# Power_and_system_Page_7.net
KiCad netlist of a schematic drawn in Altium Designer
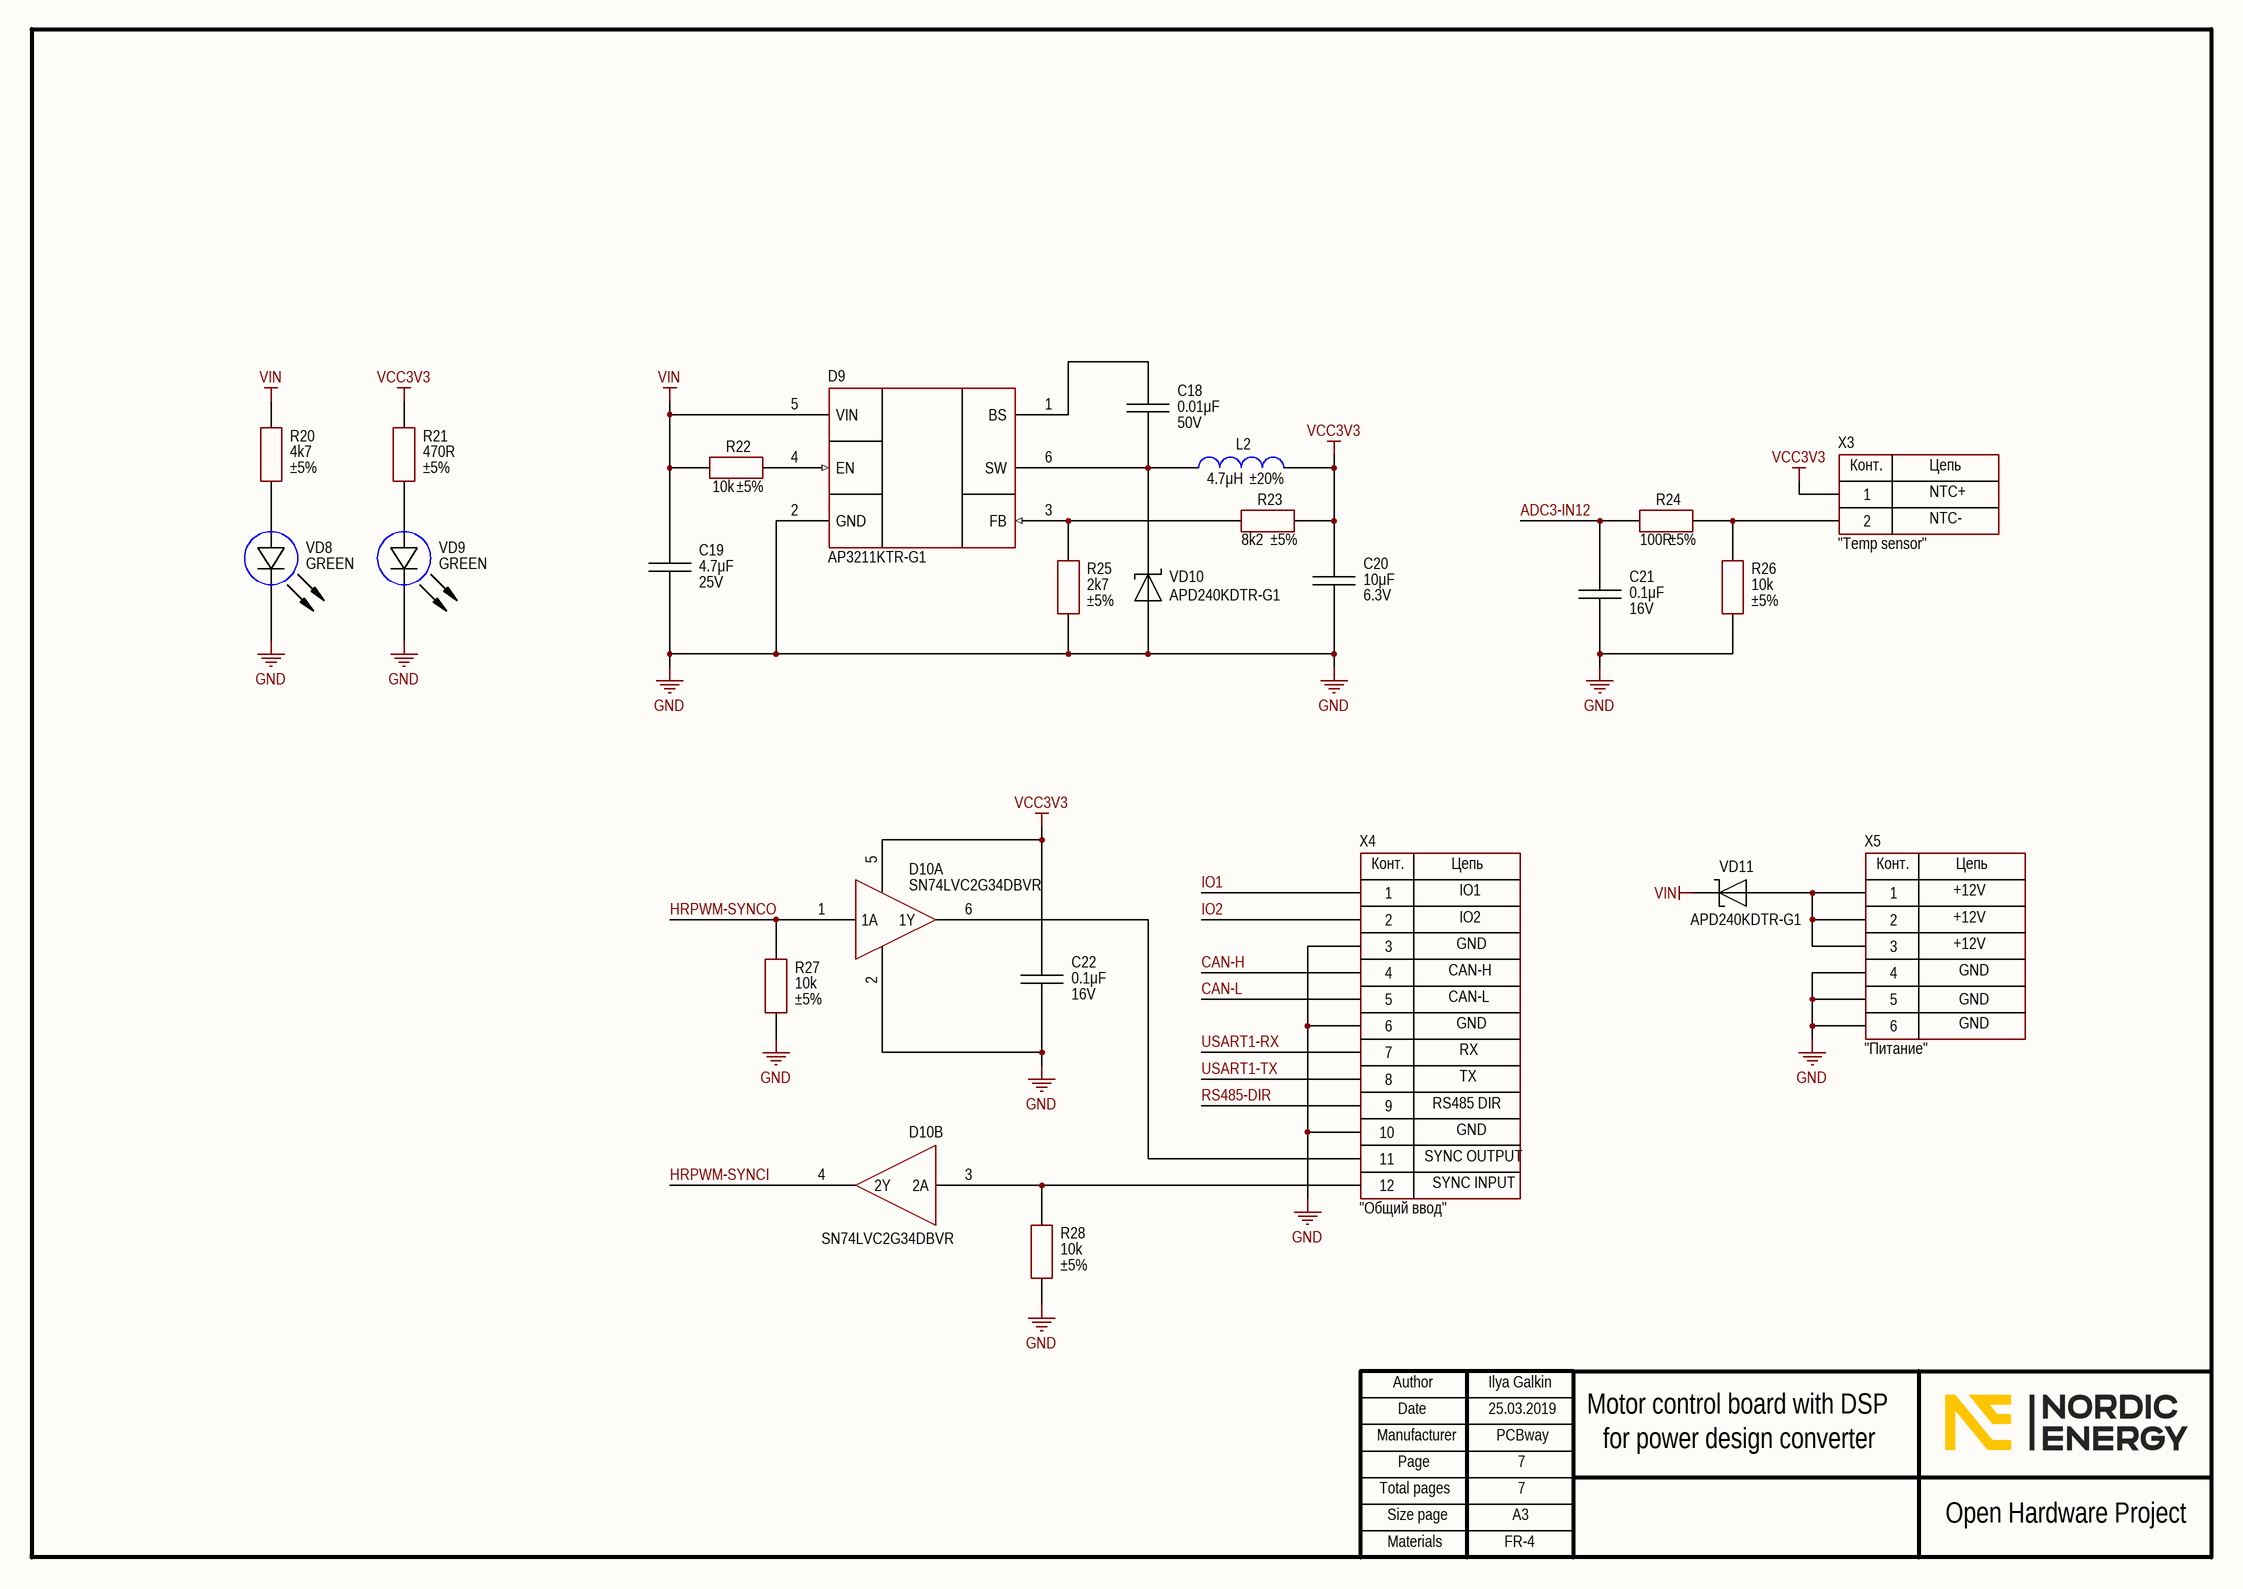
[diagram p0: Power and system. Page 7.SchDoc]

(export (version "E")
  (design (tool "Eeschema 10.0.6"))
  (components
    (comp (ref "C18")
      (value "0.01μF")
      (footprint "CAP: 0805")
      (fields
        (field (name "MANUFACTURER") "Yageo")
        (field (name "PARTNUMBER") "CC0805KRX7R9BB103")
        (field (name "VALUEMANUFACTURERPARTNUMBER") "Ceramic capacitor, 0.01μF, X7R, ±10%, 50V, 0805, -55...+125°C")
        (field (name "VOLTAGE") "50V")
      )
      (libsource (lib "Capacitor") (part "Ceramic_0805"))
    )
    (comp (ref "C19")
      (value "4.7μF")
      (footprint "CAP: 0805")
      (fields
        (field (name "MANUFACTURER") "Samsung")
        (field (name "PARTNUMBER") "CL21B475KAFNNNE")
        (field (name "VALUEMANUFACTURERPARTNUMBER") "Ceramic capacitor, 4.7μF, X7R, ±10%, 25V, 0805, -55...+125°C")
        (field (name "VOLTAGE") "25V")
      )
      (libsource (lib "Capacitor") (part "Ceramic_0805"))
    )
    (comp (ref "C20")
      (value "10μF")
      (footprint "CAP: 0805")
      (fields
        (field (name "MANUFACTURER") "Samsung")
        (field (name "PARTNUMBER") "CL21B106KQQNNNE")
        (field (name "VALUEMANUFACTURERPARTNUMBER") "Ceramic capacitor, 10μF, X7R, ±10%, 6.3V, 0805, -55...+125°C")
        (field (name "VOLTAGE") "6.3V")
      )
      (libsource (lib "Capacitor") (part "Ceramic_0805"))
    )
    (comp (ref "C21")
      (value "0.1μF")
      (footprint "CAP: 0805")
      (fields
        (field (name "MANUFACTURER") "Yageo")
        (field (name "PARTNUMBER") "CC0805KRX7R7BB104")
        (field (name "VALUEMANUFACTURERPARTNUMBER") "Ceramic capacitor, 0.1μF, X7R, ±10%, 16V, 0805, -55...+125°C")
        (field (name "VOLTAGE") "16V")
      )
      (libsource (lib "Capacitor") (part "Ceramic_0805"))
    )
    (comp (ref "C22")
      (value "0.1μF")
      (footprint "CAP: 0805")
      (fields
        (field (name "MANUFACTURER") "Yageo")
        (field (name "PARTNUMBER") "CC0805KRX7R7BB104")
        (field (name "VALUEMANUFACTURERPARTNUMBER") "Ceramic capacitor, 0.1μF, X7R, ±10%, 16V, 0805, -55...+125°C")
        (field (name "VOLTAGE") "16V")
      )
      (libsource (lib "Capacitor") (part "Ceramic_0805"))
    )
    (comp (ref "D9")
      (value "~")
      (footprint "SOT23-6")
      (description "Buck converter")
      (fields
        (field (name "MANUFACTURER") "Diodes Incorporated")
        (field (name "VALUEMANUFACTURERPARTNUMBER") "DC/DC buck converter, input 4.5...18V, 1.4MHz, output 0.81...15V, 1.5A, -40...+85°C, SOT23-6")
        (field (name "PARTNUMBER") "AP3211KTR-G1")
      )
      (libsource (lib "IC. Power supply") (part "AP3211KTR-G1"))
    )
    (comp (ref "D10")
      (value "~")
      (footprint "SOT23-6")
      (description "Buffer")
      (fields
        (field (name "MANUFACTURER") "Texas Instruments")
        (field (name "VALUEMANUFACTURERPARTNUMBER") "IC logic buffer, 1.65...5.5V, -40...+125°C, SOT23-6")
        (field (name "PARTNUMBER") "SN74LVC2G34DBVR")
      )
      (libsource (lib "IC. Logic") (part "SN74LVC2G34DBVR"))
    )
    (comp (ref "L2")
      (value "4.7μH")
      (footprint "IND: SRP2510A")
      (fields
        (field (name "MANUFACTURER") "Bourns")
        (field (name "PARTNUMBER") "SRP2510A-4R7M")
        (field (name "VALUEMANUFACTURERPARTNUMBER") "Fixed inductor, 4.7μH, ±20%, SRP2510A, 1.36A, -40...+125°C")
        (field (name "TOLERANCE") "±20%")
      )
      (libsource (lib "Inductor") (part "Inductor_SRP2510A"))
    )
    (comp (ref "R20")
      (value "4k7")
      (footprint "RES: 0805")
      (fields
        (field (name "MANUFACTURER") "Yageo")
        (field (name "PARTNUMBER") "RC0805JR-074K7L")
        (field (name "VALUEMANUFACTURERPARTNUMBER") "Resistor film, 4k7, ±5%, 0805, 0.125W, -55...+125°C")
        (field (name "TOLERANCE") "±5%")
      )
      (libsource (lib "Resistor") (part "Resistor_0805"))
    )
    (comp (ref "R21")
      (value "470R")
      (footprint "RES: 0805")
      (fields
        (field (name "MANUFACTURER") "Yageo")
        (field (name "PARTNUMBER") "RC0805JR-07470RL")
        (field (name "VALUEMANUFACTURERPARTNUMBER") "Resistor film, 470R, ±5%, 0805, 0.125W, -55...+125°C")
        (field (name "TOLERANCE") "±5%")
      )
      (libsource (lib "") (part "Resistor_0805_2"))
    )
    (comp (ref "R22")
      (value "10k")
      (footprint "RES: 0805")
      (fields
        (field (name "MANUFACTURER") "Yageo")
        (field (name "PARTNUMBER") "RC0805JR-0710KL")
        (field (name "VALUEMANUFACTURERPARTNUMBER") "Resistor film, 10k, ±5%, 0805, 0.125W, -55...+125°C")
        (field (name "TOLERANCE") "±5%")
      )
      (libsource (lib "") (part "Resistor_0805_1"))
    )
    (comp (ref "R23")
      (value "8k2")
      (footprint "RES: 0805")
      (fields
        (field (name "MANUFACTURER") "Yageo")
        (field (name "PARTNUMBER") "RC0805JR-078K2L")
        (field (name "VALUEMANUFACTURERPARTNUMBER") "Resistor film, 8k2, ±5%, 0805, 0.125W, -55...+125°C")
        (field (name "TOLERANCE") "±5%")
      )
      (libsource (lib "") (part "Resistor_0805_1"))
    )
    (comp (ref "R24")
      (value "100R")
      (footprint "RES: 0805")
      (fields
        (field (name "MANUFACTURER") "Yageo")
        (field (name "PARTNUMBER") "RC0805JR-07100RL")
        (field (name "VALUEMANUFACTURERPARTNUMBER") "Resistor film, 100R, ±5%, 0805, 0.125W, -55...+125°C")
        (field (name "TOLERANCE") "±5%")
      )
      (libsource (lib "") (part "Resistor_0805_1"))
    )
    (comp (ref "R25")
      (value "2k7")
      (footprint "RES: 0805")
      (fields
        (field (name "MANUFACTURER") "Yageo")
        (field (name "PARTNUMBER") "RC0805JR-072K7L")
        (field (name "VALUEMANUFACTURERPARTNUMBER") "Resistor film, 2k7, ±5%, 0805, 0.125W, -55...+125°C")
        (field (name "TOLERANCE") "±5%")
      )
      (libsource (lib "") (part "Resistor_0805_2"))
    )
    (comp (ref "R26")
      (value "10k")
      (footprint "RES: 0805")
      (fields
        (field (name "MANUFACTURER") "Yageo")
        (field (name "PARTNUMBER") "RC0805JR-0710KL")
        (field (name "VALUEMANUFACTURERPARTNUMBER") "Resistor film, 10k, ±5%, 0805, 0.125W, -55...+125°C")
        (field (name "TOLERANCE") "±5%")
      )
      (libsource (lib "") (part "Resistor_0805_2"))
    )
    (comp (ref "R27")
      (value "10k")
      (footprint "RES: 0805")
      (fields
        (field (name "MANUFACTURER") "Yageo")
        (field (name "PARTNUMBER") "RC0805JR-0710KL")
        (field (name "VALUEMANUFACTURERPARTNUMBER") "Resistor film, 10k, ±5%, 0805, 0.125W, -55...+125°C")
        (field (name "TOLERANCE") "±5%")
      )
      (libsource (lib "Resistor") (part "Resistor_0805"))
    )
    (comp (ref "R28")
      (value "10k")
      (footprint "RES: 0805")
      (fields
        (field (name "MANUFACTURER") "Yageo")
        (field (name "PARTNUMBER") "RC0805JR-0710KL")
        (field (name "VALUEMANUFACTURERPARTNUMBER") "Resistor film, 10k, ±5%, 0805, 0.125W, -55...+125°C")
        (field (name "TOLERANCE") "±5%")
      )
      (libsource (lib "Resistor") (part "Resistor_0805"))
    )
    (comp (ref "VD8")
      (value "~")
      (footprint "LED: 0603G")
      (fields
        (field (name "MANUFACTURER") "Wurth")
        (field (name "VALUEMANUFACTURERPARTNUMBER") "LED, 20mA, 2V, 0805, -55...+150°C")
        (field (name "PARTNUMBER") "150080VS75000")
        (field (name "COLOR") "GREEN")
      )
      (libsource (lib "Diode") (part "LED_single"))
    )
    (comp (ref "VD9")
      (value "~")
      (footprint "LED: 0603G")
      (fields
        (field (name "MANUFACTURER") "Wurth")
        (field (name "VALUEMANUFACTURERPARTNUMBER") "LED, 20mA, 2V, 0805, -55...+150°C")
        (field (name "PARTNUMBER") "150080VS75000")
        (field (name "COLOR") "GREEN")
      )
      (libsource (lib "Diode") (part "LED_single"))
    )
    (comp (ref "VD10")
      (value "~")
      (footprint "DIODE: SOD123")
      (fields
        (field (name "MANUFACTURER") "Diodes Incorporated")
        (field (name "VALUEMANUFACTURERPARTNUMBER") "Schottky diode, 40V, 2A, 500mV, 15pF, SOD-123, -55...+150°C")
        (field (name "VOLTAGE") "40V")
        (field (name "PARTNUMBER") "APD240KDTR-G1")
      )
      (libsource (lib "Diode") (part "Schottky_single"))
    )
    (comp (ref "VD11")
      (value "~")
      (footprint "DIODE: SOD123")
      (fields
        (field (name "MANUFACTURER") "Diodes Incorporated")
        (field (name "VALUEMANUFACTURERPARTNUMBER") "Schottky diode, 40V, 2A, 500mV, 15pF, SOD-123, -55...+150°C")
        (field (name "VOLTAGE") "40V")
        (field (name "PARTNUMBER") "APD240KDTR-G1")
      )
      (libsource (lib "Diode") (part "Schottky_single"))
    )
    (comp (ref "X3")
      (value "~")
      (footprint "CON: PLS-2")
      (fields
        (field (name "MANUFACTURER") "Connfly")
        (field (name "VALUEMANUFACTURERPARTNUMBER") "Connector, 2pin, 2.54mm, 500VAC, 3A")
        (field (name "PARTNUMBER") "PLS-2")
        (field (name "COMMENTTEXT") "\"Temp sensor\"")
      )
      (libsource (lib "Connector") (part "PLS-2"))
    )
    (comp (ref "X4")
      (value "~")
      (footprint "CON: PBD-12")
      (fields
        (field (name "MANUFACTURER") "Connfly")
        (field (name "VALUEMANUFACTURERPARTNUMBER") "Connector, 12pin, 2.54mm, 500VAC, 3A")
        (field (name "PARTNUMBER") "PBD-12")
        (field (name "COMMENTTEXT") "\"Общий ввод\"")
      )
      (libsource (lib "Connector") (part "PBD-12"))
    )
    (comp (ref "X5")
      (value "~")
      (footprint "CON: PLD-6")
      (fields
        (field (name "MANUFACTURER") "Connfly")
        (field (name "VALUEMANUFACTURERPARTNUMBER") "Connector, 6pin, 2.54mm, 500VAC, 3A")
        (field (name "PARTNUMBER") "PLD-6")
        (field (name "COMMENTTEXT") "\"Питание\"")
      )
      (libsource (lib "Connector") (part "PLD-6"))
    )
  )
  (nets
    (net (code "1") (name "/ADC3-IN12") (class "Default")
      (node (ref "C21") (pin "2") (pinfunction "2_2") (pintype "power_in"))
      (node (ref "R24") (pin "1") (pinfunction "1_1") (pintype "passive"))
    )
    (net (code "2") (name "/CAN-H") (class "Default")
      (node (ref "X4") (pin "4") (pinfunction "4_4") (pintype "power_in"))
    )
    (net (code "3") (name "/CAN-L") (class "Default")
      (node (ref "X4") (pin "5") (pinfunction "5_5") (pintype "power_in"))
    )
    (net (code "4") (name "/HRPWM-SYNCI") (class "Default")
      (node (ref "D10") (pin "4") (pinfunction "2Y_4") (pintype "passive"))
    )
    (net (code "5") (name "/HRPWM-SYNCO") (class "Default")
      (node (ref "D10") (pin "1") (pinfunction "1A_1") (pintype "passive"))
      (node (ref "R27") (pin "1") (pinfunction "1_1") (pintype "passive"))
    )
    (net (code "6") (name "/IO1") (class "Default")
      (node (ref "X4") (pin "1") (pinfunction "1_1") (pintype "passive"))
    )
    (net (code "7") (name "/IO2") (class "Default")
      (node (ref "X4") (pin "2") (pinfunction "2_2") (pintype "passive"))
    )
    (net (code "8") (name "/RS485-DIR") (class "Default")
      (node (ref "X4") (pin "9") (pinfunction "9_9") (pintype "power_in"))
    )
    (net (code "9") (name "/USART1-RX") (class "Default")
      (node (ref "X4") (pin "7") (pinfunction "7_7") (pintype "power_in"))
    )
    (net (code "10") (name "/USART1-TX") (class "Default")
      (node (ref "X4") (pin "8") (pinfunction "8_8") (pintype "power_in"))
    )
    (net (code "11") (name "GND") (class "Default")
      (node (ref "C19") (pin "1") (pinfunction "1_1") (pintype "power_in"))
      (node (ref "C20") (pin "1") (pinfunction "1_1") (pintype "power_in"))
      (node (ref "C21") (pin "1") (pinfunction "1_1") (pintype "power_in"))
      (node (ref "C22") (pin "1") (pinfunction "1_1") (pintype "power_in"))
      (node (ref "D10") (pin "2") (pintype "passive"))
      (node (ref "D9") (pin "2") (pinfunction "GND_2") (pintype "passive"))
      (node (ref "R25") (pin "1") (pinfunction "1_1") (pintype "passive"))
      (node (ref "R26") (pin "1") (pinfunction "1_1") (pintype "passive"))
      (node (ref "R27") (pin "2") (pinfunction "2_2") (pintype "passive"))
      (node (ref "R28") (pin "2") (pinfunction "2_2") (pintype "passive"))
      (node (ref "VD10") (pin "1") (pinfunction "1_1") (pintype "passive"))
      (node (ref "VD8") (pin "2") (pinfunction "C_2") (pintype "passive"))
      (node (ref "VD9") (pin "2") (pinfunction "C_2") (pintype "passive"))
      (node (ref "X4") (pin "10") (pinfunction "10_10") (pintype "power_in"))
      (node (ref "X4") (pin "3") (pinfunction "3_3") (pintype "power_in"))
      (node (ref "X4") (pin "6") (pinfunction "6_6") (pintype "power_in"))
      (node (ref "X5") (pin "4") (pinfunction "4_4") (pintype "power_in"))
      (node (ref "X5") (pin "5") (pinfunction "5_5") (pintype "power_in"))
      (node (ref "X5") (pin "6") (pinfunction "6_6") (pintype "power_in"))
    )
    (net (code "12") (name "Net-(D9-BS)") (class "Default")
      (node (ref "C18") (pin "2") (pinfunction "2_2") (pintype "power_in"))
      (node (ref "D9") (pin "1") (pinfunction "BS_1") (pintype "passive"))
    )
    (net (code "13") (name "Net-(D9-EN)") (class "Default")
      (node (ref "D9") (pin "4") (pinfunction "EN_4") (pintype "input"))
      (node (ref "R22") (pin "2") (pinfunction "2_2") (pintype "passive"))
    )
    (net (code "14") (name "Net-(D9-FB)") (class "Default")
      (node (ref "D9") (pin "3") (pinfunction "FB_3") (pintype "input"))
      (node (ref "R23") (pin "1") (pinfunction "1_1") (pintype "passive"))
      (node (ref "R25") (pin "2") (pinfunction "2_2") (pintype "passive"))
    )
    (net (code "15") (name "Net-(D9-SW)") (class "Default")
      (node (ref "C18") (pin "1") (pinfunction "1_1") (pintype "power_in"))
      (node (ref "D9") (pin "6") (pinfunction "SW_6") (pintype "passive"))
      (node (ref "L2") (pin "2") (pinfunction "2_2") (pintype "passive"))
      (node (ref "VD10") (pin "2") (pinfunction "2_2") (pintype "passive"))
    )
    (net (code "16") (name "Net-(D10A-1Y)") (class "Default")
      (node (ref "D10") (pin "6") (pinfunction "1Y_6") (pintype "passive"))
      (node (ref "X4") (pin "11") (pinfunction "11_11") (pintype "power_in"))
    )
    (net (code "17") (name "Net-(D10B-2A)") (class "Default")
      (node (ref "D10") (pin "3") (pinfunction "2A_3") (pintype "passive"))
      (node (ref "R28") (pin "1") (pinfunction "1_1") (pintype "passive"))
      (node (ref "X4") (pin "12") (pinfunction "12_12") (pintype "power_in"))
    )
    (net (code "18") (name "Net-(R24-Pad2)") (class "Default")
      (node (ref "R24") (pin "2") (pinfunction "2_2") (pintype "passive"))
      (node (ref "R26") (pin "2") (pinfunction "2_2") (pintype "passive"))
      (node (ref "X3") (pin "2") (pinfunction "2_2") (pintype "passive"))
    )
    (net (code "19") (name "Net-(VD8-A)") (class "Default")
      (node (ref "R20") (pin "2") (pinfunction "2_2") (pintype "passive"))
      (node (ref "VD8") (pin "1") (pinfunction "A_1") (pintype "passive"))
    )
    (net (code "20") (name "Net-(VD9-A)") (class "Default")
      (node (ref "R21") (pin "1") (pinfunction "1_1") (pintype "passive"))
      (node (ref "VD9") (pin "1") (pinfunction "A_1") (pintype "passive"))
    )
    (net (code "21") (name "Net-(VD11-Pad1)") (class "Default")
      (node (ref "VD11") (pin "1") (pinfunction "1_1") (pintype "passive"))
      (node (ref "X5") (pin "1") (pinfunction "1_1") (pintype "passive"))
      (node (ref "X5") (pin "2") (pinfunction "2_2") (pintype "passive"))
      (node (ref "X5") (pin "3") (pinfunction "3_3") (pintype "power_in"))
    )
    (net (code "22") (name "VCC3V3") (class "Default")
      (node (ref "C20") (pin "2") (pinfunction "2_2") (pintype "power_in"))
      (node (ref "C22") (pin "2") (pinfunction "2_2") (pintype "power_in"))
      (node (ref "D10") (pin "5") (pintype "passive"))
      (node (ref "L2") (pin "1") (pinfunction "1_1") (pintype "passive"))
      (node (ref "R21") (pin "2") (pinfunction "2_2") (pintype "passive"))
      (node (ref "R23") (pin "2") (pinfunction "2_2") (pintype "passive"))
      (node (ref "X3") (pin "1") (pinfunction "1_1") (pintype "passive"))
    )
    (net (code "23") (name "VIN") (class "Default")
      (node (ref "C19") (pin "2") (pinfunction "2_2") (pintype "power_in"))
      (node (ref "D9") (pin "5") (pinfunction "VIN_5") (pintype "passive"))
      (node (ref "R20") (pin "1") (pinfunction "1_1") (pintype "passive"))
      (node (ref "R22") (pin "1") (pinfunction "1_1") (pintype "passive"))
      (node (ref "VD11") (pin "2") (pinfunction "2_2") (pintype "passive"))
    )
  )
)
